# LME49600_HPA.net
KiCad netlist of a schematic drawn in EAGLE
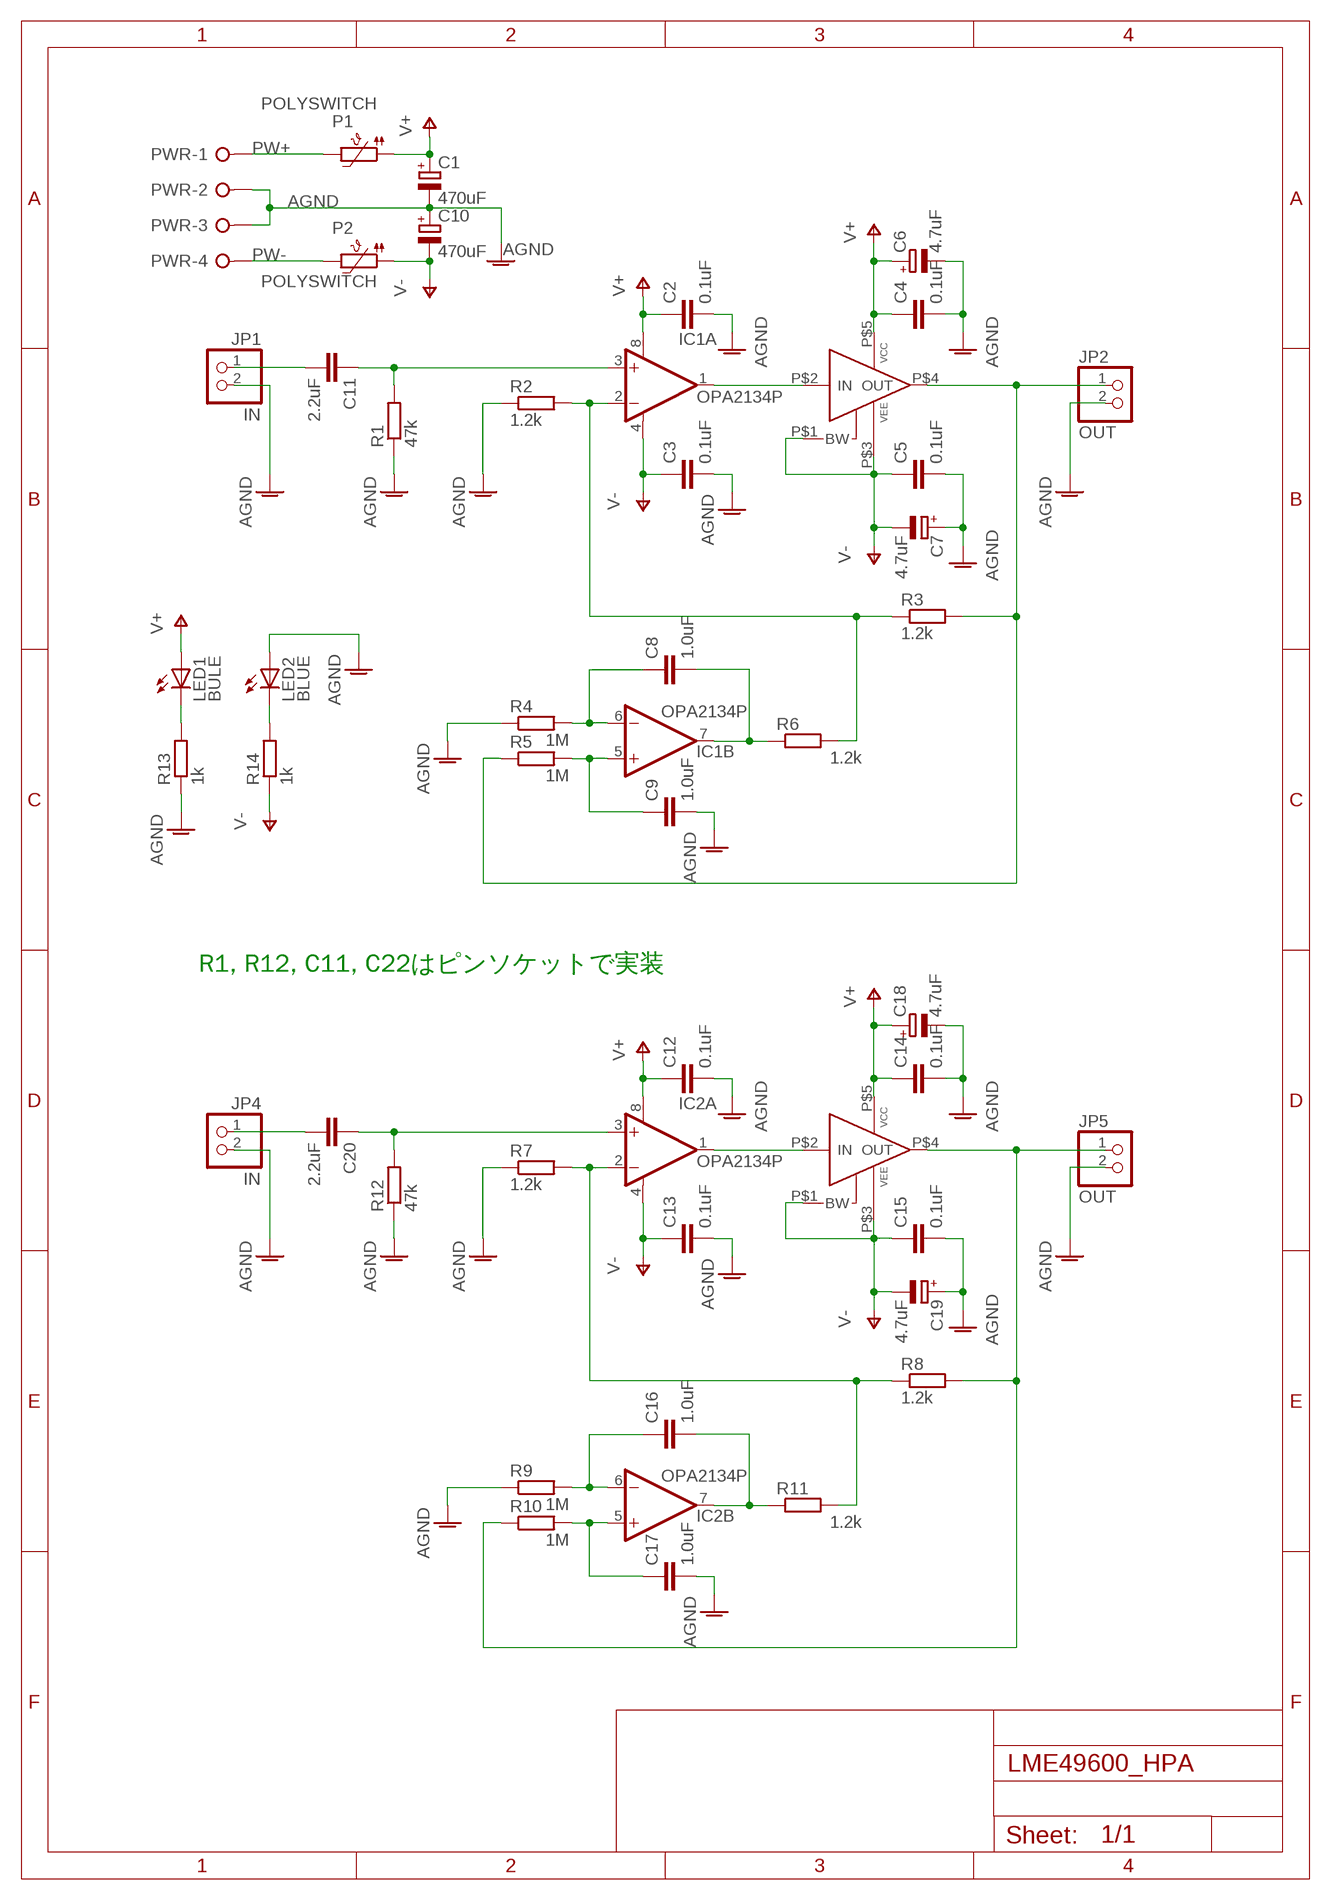
[diagram p0: schematic, sheet 1]

(export (version "E")
  (design (tool "Eeschema 10.0.6"))
  (components
    (comp (ref "C1")
      (value "470uF")
      (footprint "eagle-import:E7,5-16")
      (libsource (lib "eagle-import") (part "CPOL-EUE7.5-16"))
    )
    (comp (ref "C2")
      (value "0.1uF")
      (footprint "eagle-import:C075-042X103")
      (libsource (lib "eagle-import") (part "C-EU075-042X103"))
    )
    (comp (ref "C3")
      (value "0.1uF")
      (footprint "eagle-import:C075-042X103")
      (libsource (lib "eagle-import") (part "C-EU075-042X103"))
    )
    (comp (ref "C4")
      (value "0.1uF")
      (footprint "eagle-import:C050H075X075")
      (libsource (lib "eagle-import") (part "C-EU050H075X075"))
    )
    (comp (ref "C5")
      (value "0.1uF")
      (footprint "eagle-import:C050H075X075")
      (libsource (lib "eagle-import") (part "C-EU050H075X075"))
    )
    (comp (ref "C6")
      (value "4.7uF")
      (footprint "eagle-import:E2-4")
      (libsource (lib "eagle-import") (part "CPOL-EUE2-4"))
    )
    (comp (ref "C7")
      (value "4.7uF")
      (footprint "eagle-import:E2-4")
      (libsource (lib "eagle-import") (part "CPOL-EUE2-4"))
    )
    (comp (ref "C8")
      (value "1.0uF")
      (footprint "eagle-import:C050-050X075")
      (libsource (lib "eagle-import") (part "C-EU050-050X075"))
    )
    (comp (ref "C9")
      (value "1.0uF")
      (footprint "eagle-import:C050-050X075")
      (libsource (lib "eagle-import") (part "C-EU050-050X075"))
    )
    (comp (ref "C10")
      (value "470uF")
      (footprint "eagle-import:E7,5-16")
      (libsource (lib "eagle-import") (part "CPOL-EUE7.5-16"))
    )
    (comp (ref "C11")
      (value "2.2uF")
      (footprint "eagle-import:C050-055X075")
      (libsource (lib "eagle-import") (part "C-EU050-055X075"))
    )
    (comp (ref "C12")
      (value "0.1uF")
      (footprint "eagle-import:C075-042X103")
      (libsource (lib "eagle-import") (part "C-EU075-042X103"))
    )
    (comp (ref "C13")
      (value "0.1uF")
      (footprint "eagle-import:C075-042X103")
      (libsource (lib "eagle-import") (part "C-EU075-042X103"))
    )
    (comp (ref "C14")
      (value "0.1uF")
      (footprint "eagle-import:C050H075X075")
      (libsource (lib "eagle-import") (part "C-EU050H075X075"))
    )
    (comp (ref "C15")
      (value "0.1uF")
      (footprint "eagle-import:C050H075X075")
      (libsource (lib "eagle-import") (part "C-EU050H075X075"))
    )
    (comp (ref "C16")
      (value "1.0uF")
      (footprint "eagle-import:C050-050X075")
      (libsource (lib "eagle-import") (part "C-EU050-050X075"))
    )
    (comp (ref "C17")
      (value "1.0uF")
      (footprint "eagle-import:C050-050X075")
      (libsource (lib "eagle-import") (part "C-EU050-050X075"))
    )
    (comp (ref "C18")
      (value "4.7uF")
      (footprint "eagle-import:E2-4")
      (libsource (lib "eagle-import") (part "CPOL-EUE2-4"))
    )
    (comp (ref "C19")
      (value "4.7uF")
      (footprint "eagle-import:E2-4")
      (libsource (lib "eagle-import") (part "CPOL-EUE2-4"))
    )
    (comp (ref "C20")
      (value "2.2uF")
      (footprint "eagle-import:C050-055X075")
      (libsource (lib "eagle-import") (part "C-EU050-055X075"))
    )
    (comp (ref "IC1")
      (value "OPA2134P")
      (footprint "eagle-import:DIL08")
      (fields (field (name "MF") "TEXAS INSTRUMENTS") (field (name "MPN") "OPA2134PA"))
      (libsource (lib "eagle-import") (part "OPA2134P"))
    )
    (comp (ref "IC2")
      (value "OPA2134P")
      (footprint "eagle-import:DIL08")
      (fields (field (name "MF") "TEXAS INSTRUMENTS") (field (name "MPN") "OPA2134PA"))
      (libsource (lib "eagle-import") (part "OPA2134P"))
    )
    (comp (ref "JP1")
      (value "IN")
      (footprint "eagle-import:1X02")
      (libsource (lib "eagle-import") (part "PINHD-1X2"))
    )
    (comp (ref "JP2")
      (value "OUT")
      (footprint "eagle-import:1X02")
      (libsource (lib "eagle-import") (part "PINHD-1X2"))
    )
    (comp (ref "JP4")
      (value "IN")
      (footprint "eagle-import:1X02")
      (libsource (lib "eagle-import") (part "PINHD-1X2"))
    )
    (comp (ref "JP5")
      (value "OUT")
      (footprint "eagle-import:1X02")
      (libsource (lib "eagle-import") (part "PINHD-1X2"))
    )
    (comp (ref "LED1")
      (value "BULE")
      (footprint "eagle-import:LED3MM")
      (libsource (lib "eagle-import") (part "LED3MM"))
    )
    (comp (ref "LED2")
      (value "BLUE")
      (footprint "eagle-import:LED3MM")
      (libsource (lib "eagle-import") (part "LED3MM"))
    )
    (comp (ref "P1")
      (value "POLYSWITCH")
      (footprint "eagle-import:POLYSWITCH")
      (libsource (lib "eagle-import") (part "POLYSWITCH"))
    )
    (comp (ref "P2")
      (value "POLYSWITCH")
      (footprint "eagle-import:POLYSWITCH")
      (libsource (lib "eagle-import") (part "POLYSWITCH"))
    )
    (comp (ref "PWR")
      (value "W237-04P")
      (footprint "eagle-import:W237-4P")
      (libsource (lib "eagle-import") (part "W237-04P"))
    )
    (comp (ref "R1")
      (value "47k")
      (footprint "eagle-import:0207_7")
      (libsource (lib "eagle-import") (part "R-EU_0207/7"))
    )
    (comp (ref "R2")
      (value "1.2k")
      (footprint "eagle-import:0207_7")
      (libsource (lib "eagle-import") (part "R-EU_0207/7"))
    )
    (comp (ref "R3")
      (value "1.2k")
      (footprint "eagle-import:0207_7")
      (libsource (lib "eagle-import") (part "R-EU_0207/7"))
    )
    (comp (ref "R4")
      (value "1M")
      (footprint "eagle-import:0207_7")
      (libsource (lib "eagle-import") (part "R-EU_0207/7"))
    )
    (comp (ref "R5")
      (value "1M")
      (footprint "eagle-import:0207_7")
      (libsource (lib "eagle-import") (part "R-EU_0207/7"))
    )
    (comp (ref "R6")
      (value "1.2k")
      (footprint "eagle-import:0207_7")
      (libsource (lib "eagle-import") (part "R-EU_0207/7"))
    )
    (comp (ref "R7")
      (value "1.2k")
      (footprint "eagle-import:0207_7")
      (libsource (lib "eagle-import") (part "R-EU_0207/7"))
    )
    (comp (ref "R8")
      (value "1.2k")
      (footprint "eagle-import:0207_7")
      (libsource (lib "eagle-import") (part "R-EU_0207/7"))
    )
    (comp (ref "R9")
      (value "1M")
      (footprint "eagle-import:0207_7")
      (libsource (lib "eagle-import") (part "R-EU_0207/7"))
    )
    (comp (ref "R10")
      (value "1M")
      (footprint "eagle-import:0207_7")
      (libsource (lib "eagle-import") (part "R-EU_0207/7"))
    )
    (comp (ref "R11")
      (value "1.2k")
      (footprint "eagle-import:0207_7")
      (libsource (lib "eagle-import") (part "R-EU_0207/7"))
    )
    (comp (ref "R12")
      (value "47k")
      (footprint "eagle-import:0207_7")
      (libsource (lib "eagle-import") (part "R-EU_0207/7"))
    )
    (comp (ref "R13")
      (value "1k")
      (footprint "eagle-import:0207_7")
      (libsource (lib "eagle-import") (part "R-EU_0207/7"))
    )
    (comp (ref "R14")
      (value "1k")
      (footprint "eagle-import:0207_7")
      (libsource (lib "eagle-import") (part "R-EU_0207/7"))
    )
    (comp (ref "U$1")
      (value "LME49600-BRD2")
      (footprint "eagle-import:SIP5-9")
      (libsource (lib "eagle-import") (part "LME49600-BRD2"))
    )
    (comp (ref "U$2")
      (value "LME49600-BRD2")
      (footprint "eagle-import:SIP5-9")
      (libsource (lib "eagle-import") (part "LME49600-BRD2"))
    )
  )
  (nets
    (net (code "1") (name "/PW+") (class "Default")
      (node (ref "P1") (pin "2") (pinfunction "2_2") (pintype "passive"))
      (node (ref "PWR") (pin "1") (pinfunction "KL_1") (pintype "passive"))
    )
    (net (code "2") (name "/PW-") (class "Default")
      (node (ref "P2") (pin "2") (pinfunction "2_2") (pintype "passive"))
      (node (ref "PWR") (pin "4") (pinfunction "KL_4") (pintype "passive"))
    )
    (net (code "3") (name "AGND") (class "Default")
      (node (ref "C1") (pin "-") (pinfunction "-_-") (pintype "passive"))
      (node (ref "C10") (pin "+") (pinfunction "+_+") (pintype "passive"))
      (node (ref "C12") (pin "2") (pinfunction "2_2") (pintype "passive"))
      (node (ref "C13") (pin "2") (pinfunction "2_2") (pintype "passive"))
      (node (ref "C14") (pin "2") (pinfunction "2_2") (pintype "passive"))
      (node (ref "C15") (pin "2") (pinfunction "2_2") (pintype "passive"))
      (node (ref "C17") (pin "2") (pinfunction "2_2") (pintype "passive"))
      (node (ref "C18") (pin "-") (pinfunction "-_-") (pintype "passive"))
      (node (ref "C19") (pin "+") (pinfunction "+_+") (pintype "passive"))
      (node (ref "C2") (pin "2") (pinfunction "2_2") (pintype "passive"))
      (node (ref "C3") (pin "2") (pinfunction "2_2") (pintype "passive"))
      (node (ref "C4") (pin "2") (pinfunction "2_2") (pintype "passive"))
      (node (ref "C5") (pin "2") (pinfunction "2_2") (pintype "passive"))
      (node (ref "C6") (pin "-") (pinfunction "-_-") (pintype "passive"))
      (node (ref "C7") (pin "+") (pinfunction "+_+") (pintype "passive"))
      (node (ref "C9") (pin "2") (pinfunction "2_2") (pintype "passive"))
      (node (ref "JP1") (pin "2") (pinfunction "2_2") (pintype "passive"))
      (node (ref "JP2") (pin "2") (pinfunction "2_2") (pintype "passive"))
      (node (ref "JP4") (pin "2") (pinfunction "2_2") (pintype "passive"))
      (node (ref "JP5") (pin "2") (pinfunction "2_2") (pintype "passive"))
      (node (ref "LED2") (pin "A") (pinfunction "A_A") (pintype "passive"))
      (node (ref "PWR") (pin "2") (pinfunction "KL_2") (pintype "passive"))
      (node (ref "PWR") (pin "3") (pinfunction "KL_3") (pintype "passive"))
      (node (ref "R1") (pin "1") (pinfunction "1_1") (pintype "passive"))
      (node (ref "R12") (pin "1") (pinfunction "1_1") (pintype "passive"))
      (node (ref "R13") (pin "1") (pinfunction "1_1") (pintype "passive"))
      (node (ref "R2") (pin "1") (pinfunction "1_1") (pintype "passive"))
      (node (ref "R4") (pin "1") (pinfunction "1_1") (pintype "passive"))
      (node (ref "R7") (pin "1") (pinfunction "1_1") (pintype "passive"))
      (node (ref "R9") (pin "1") (pinfunction "1_1") (pintype "passive"))
    )
    (net (code "4") (name "Net-(C11-Pad2)") (class "Default")
      (node (ref "C11") (pin "2") (pinfunction "2_2") (pintype "passive"))
      (node (ref "JP1") (pin "1") (pinfunction "1_1") (pintype "passive"))
    )
    (net (code "5") (name "Net-(C20-Pad2)") (class "Default")
      (node (ref "C20") (pin "2") (pinfunction "2_2") (pintype "passive"))
      (node (ref "JP4") (pin "1") (pinfunction "1_1") (pintype "passive"))
    )
    (net (code "6") (name "Net-(IC1A-+IN)") (class "Default")
      (node (ref "C11") (pin "1") (pinfunction "1_1") (pintype "passive"))
      (node (ref "IC1") (pin "3") (pinfunction "+IN_3") (pintype "input"))
      (node (ref "R1") (pin "2") (pinfunction "2_2") (pintype "passive"))
    )
    (net (code "7") (name "Net-(IC1A--IN)") (class "Default")
      (node (ref "IC1") (pin "2") (pinfunction "-IN_2") (pintype "input"))
      (node (ref "R2") (pin "2") (pinfunction "2_2") (pintype "passive"))
      (node (ref "R3") (pin "1") (pinfunction "1_1") (pintype "passive"))
      (node (ref "R6") (pin "2") (pinfunction "2_2") (pintype "passive"))
    )
    (net (code "8") (name "Net-(IC1A-OUT)") (class "Default")
      (node (ref "IC1") (pin "1") (pinfunction "OUT_1") (pintype "output"))
      (node (ref "U$1") (pin "P$2") (pinfunction "IN_P$2") (pintype "input"))
    )
    (net (code "9") (name "Net-(IC1B-+IN)") (class "Default")
      (node (ref "C9") (pin "1") (pinfunction "1_1") (pintype "passive"))
      (node (ref "IC1") (pin "5") (pinfunction "+IN_5") (pintype "input"))
      (node (ref "R5") (pin "2") (pinfunction "2_2") (pintype "passive"))
    )
    (net (code "10") (name "Net-(IC1B--IN)") (class "Default")
      (node (ref "C8") (pin "1") (pinfunction "1_1") (pintype "passive"))
      (node (ref "IC1") (pin "6") (pinfunction "-IN_6") (pintype "input"))
      (node (ref "R4") (pin "2") (pinfunction "2_2") (pintype "passive"))
    )
    (net (code "11") (name "Net-(IC1B-OUT)") (class "Default")
      (node (ref "C8") (pin "2") (pinfunction "2_2") (pintype "passive"))
      (node (ref "IC1") (pin "7") (pinfunction "OUT_7") (pintype "output"))
      (node (ref "R6") (pin "1") (pinfunction "1_1") (pintype "passive"))
    )
    (net (code "12") (name "Net-(IC2A-+IN)") (class "Default")
      (node (ref "C20") (pin "1") (pinfunction "1_1") (pintype "passive"))
      (node (ref "IC2") (pin "3") (pinfunction "+IN_3") (pintype "input"))
      (node (ref "R12") (pin "2") (pinfunction "2_2") (pintype "passive"))
    )
    (net (code "13") (name "Net-(IC2A--IN)") (class "Default")
      (node (ref "IC2") (pin "2") (pinfunction "-IN_2") (pintype "input"))
      (node (ref "R11") (pin "2") (pinfunction "2_2") (pintype "passive"))
      (node (ref "R7") (pin "2") (pinfunction "2_2") (pintype "passive"))
      (node (ref "R8") (pin "1") (pinfunction "1_1") (pintype "passive"))
    )
    (net (code "14") (name "Net-(IC2A-OUT)") (class "Default")
      (node (ref "IC2") (pin "1") (pinfunction "OUT_1") (pintype "output"))
      (node (ref "U$2") (pin "P$2") (pinfunction "IN_P$2") (pintype "input"))
    )
    (net (code "15") (name "Net-(IC2B-+IN)") (class "Default")
      (node (ref "C17") (pin "1") (pinfunction "1_1") (pintype "passive"))
      (node (ref "IC2") (pin "5") (pinfunction "+IN_5") (pintype "input"))
      (node (ref "R10") (pin "2") (pinfunction "2_2") (pintype "passive"))
    )
    (net (code "16") (name "Net-(IC2B--IN)") (class "Default")
      (node (ref "C16") (pin "1") (pinfunction "1_1") (pintype "passive"))
      (node (ref "IC2") (pin "6") (pinfunction "-IN_6") (pintype "input"))
      (node (ref "R9") (pin "2") (pinfunction "2_2") (pintype "passive"))
    )
    (net (code "17") (name "Net-(IC2B-OUT)") (class "Default")
      (node (ref "C16") (pin "2") (pinfunction "2_2") (pintype "passive"))
      (node (ref "IC2") (pin "7") (pinfunction "OUT_7") (pintype "output"))
      (node (ref "R11") (pin "1") (pinfunction "1_1") (pintype "passive"))
    )
    (net (code "18") (name "Net-(LED1-C)") (class "Default")
      (node (ref "LED1") (pin "K") (pinfunction "C_K") (pintype "passive"))
      (node (ref "R13") (pin "2") (pinfunction "2_2") (pintype "passive"))
    )
    (net (code "19") (name "Net-(LED2-C)") (class "Default")
      (node (ref "LED2") (pin "K") (pinfunction "C_K") (pintype "passive"))
      (node (ref "R14") (pin "2") (pinfunction "2_2") (pintype "passive"))
    )
    (net (code "20") (name "Net-(U$1-OUT)") (class "Default")
      (node (ref "JP2") (pin "1") (pinfunction "1_1") (pintype "passive"))
      (node (ref "R3") (pin "2") (pinfunction "2_2") (pintype "passive"))
      (node (ref "R5") (pin "1") (pinfunction "1_1") (pintype "passive"))
      (node (ref "U$1") (pin "P$4") (pinfunction "OUT_P$4") (pintype "output"))
    )
    (net (code "21") (name "Net-(U$2-OUT)") (class "Default")
      (node (ref "JP5") (pin "1") (pinfunction "1_1") (pintype "passive"))
      (node (ref "R10") (pin "1") (pinfunction "1_1") (pintype "passive"))
      (node (ref "R8") (pin "2") (pinfunction "2_2") (pintype "passive"))
      (node (ref "U$2") (pin "P$4") (pinfunction "OUT_P$4") (pintype "output"))
    )
    (net (code "22") (name "V+") (class "Default")
      (node (ref "C1") (pin "+") (pinfunction "+_+") (pintype "passive"))
      (node (ref "C12") (pin "1") (pinfunction "1_1") (pintype "passive"))
      (node (ref "C14") (pin "1") (pinfunction "1_1") (pintype "passive"))
      (node (ref "C18") (pin "+") (pinfunction "+_+") (pintype "passive"))
      (node (ref "C2") (pin "1") (pinfunction "1_1") (pintype "passive"))
      (node (ref "C4") (pin "1") (pinfunction "1_1") (pintype "passive"))
      (node (ref "C6") (pin "+") (pinfunction "+_+") (pintype "passive"))
      (node (ref "IC1") (pin "8") (pinfunction "V+_8") (pintype "power_in"))
      (node (ref "IC2") (pin "8") (pinfunction "V+_8") (pintype "power_in"))
      (node (ref "LED1") (pin "A") (pinfunction "A_A") (pintype "passive"))
      (node (ref "P1") (pin "1") (pinfunction "1_1") (pintype "passive"))
      (node (ref "U$1") (pin "P$5") (pinfunction "VCC_P$5") (pintype "power_in"))
      (node (ref "U$2") (pin "P$5") (pinfunction "VCC_P$5") (pintype "power_in"))
    )
    (net (code "23") (name "V-") (class "Default")
      (node (ref "C10") (pin "-") (pinfunction "-_-") (pintype "passive"))
      (node (ref "C13") (pin "1") (pinfunction "1_1") (pintype "passive"))
      (node (ref "C15") (pin "1") (pinfunction "1_1") (pintype "passive"))
      (node (ref "C19") (pin "-") (pinfunction "-_-") (pintype "passive"))
      (node (ref "C3") (pin "1") (pinfunction "1_1") (pintype "passive"))
      (node (ref "C5") (pin "1") (pinfunction "1_1") (pintype "passive"))
      (node (ref "C7") (pin "-") (pinfunction "-_-") (pintype "passive"))
      (node (ref "IC1") (pin "4") (pinfunction "V-_4") (pintype "power_in"))
      (node (ref "IC2") (pin "4") (pinfunction "V-_4") (pintype "power_in"))
      (node (ref "P2") (pin "1") (pinfunction "1_1") (pintype "passive"))
      (node (ref "R14") (pin "1") (pinfunction "1_1") (pintype "passive"))
      (node (ref "U$1") (pin "P$1") (pinfunction "BW_P$1") (pintype "input"))
      (node (ref "U$1") (pin "P$3") (pinfunction "VEE_P$3") (pintype "power_in"))
      (node (ref "U$2") (pin "P$1") (pinfunction "BW_P$1") (pintype "input"))
      (node (ref "U$2") (pin "P$3") (pinfunction "VEE_P$3") (pintype "power_in"))
    )
  )
)
